# relay_interface_v2.net
KiCad netlist of a schematic drawn in EAGLE
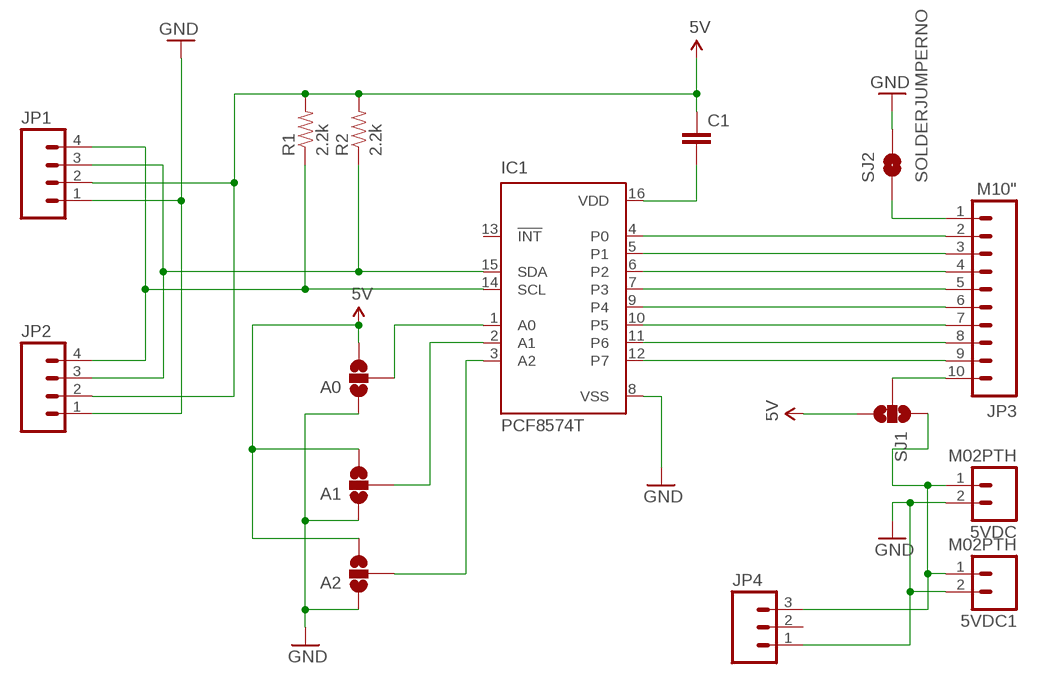
[diagram p0: schematic, sheet 1]

(export (version "E")
  (design (tool "Eeschema 10.0.6"))
  (components
    (comp (ref "5VDC")
      (value "M02PTH")
      (footprint "eagle-import:1X02")
      (libsource (lib "eagle-import") (part "M02PTH"))
    )
    (comp (ref "5VDC1")
      (value "M02PTH")
      (footprint "eagle-import:1X02")
      (libsource (lib "eagle-import") (part "M02PTH"))
    )
    (comp (ref "A0")
      (value "SOLDERJUMPER_2WAYS")
      (footprint "eagle-import:SJ_3")
      (libsource (lib "eagle-import") (part "SOLDERJUMPER_2WAYS"))
    )
    (comp (ref "A1")
      (value "SOLDERJUMPER_2WAYS")
      (footprint "eagle-import:SJ_3")
      (libsource (lib "eagle-import") (part "SOLDERJUMPER_2WAYS"))
    )
    (comp (ref "A2")
      (value "SOLDERJUMPER_2WAYS")
      (footprint "eagle-import:SJ_3")
      (libsource (lib "eagle-import") (part "SOLDERJUMPER_2WAYS"))
    )
    (comp (ref "C1")
      (value "CAPPTH2")
      (footprint "eagle-import:CAP-PTH-SMALL2")
      (libsource (lib "eagle-import") (part "CAPPTH2"))
    )
    (comp (ref "IC1")
      (value "PCF8574T")
      (footprint "eagle-import:SO16W")
      (libsource (lib "eagle-import") (part "PCF8574T"))
    )
    (comp (ref "JP1")
      (value "M04PTH")
      (footprint "eagle-import:1X04")
      (libsource (lib "eagle-import") (part "M04PTH"))
    )
    (comp (ref "JP2")
      (value "M04PTH")
      (footprint "eagle-import:1X04")
      (libsource (lib "eagle-import") (part "M04PTH"))
    )
    (comp (ref "JP3")
      (value "M10\"")
      (footprint "eagle-import:1X10")
      (libsource (lib "eagle-import") (part "M10{dblquote}"))
    )
    (comp (ref "JP4")
      (value "M03PTH")
      (footprint "eagle-import:1X03")
      (libsource (lib "eagle-import") (part "M03PTH"))
    )
    (comp (ref "R1")
      (value "2.2k")
      (footprint "eagle-import:1206")
      (libsource (lib "eagle-import") (part "RESISTOR1206"))
    )
    (comp (ref "R2")
      (value "2.2k")
      (footprint "eagle-import:1206")
      (libsource (lib "eagle-import") (part "RESISTOR1206"))
    )
    (comp (ref "SJ1")
      (value "SOLDERJUMPER_2WAYS")
      (footprint "eagle-import:SJ_3")
      (libsource (lib "eagle-import") (part "SOLDERJUMPER_2WAYS"))
    )
    (comp (ref "SJ2")
      (value "SOLDERJUMPERNO")
      (footprint "eagle-import:SJ_2S-NO")
      (libsource (lib "eagle-import") (part "SOLDERJUMPERNO"))
    )
  )
  (nets
    (net (code "1") (name "5V") (class "Default")
      (node (ref "A0") (pin "3") (pinfunction "3_3") (pintype "passive"))
      (node (ref "A1") (pin "3") (pinfunction "3_3") (pintype "passive"))
      (node (ref "A2") (pin "3") (pinfunction "3_3") (pintype "passive"))
      (node (ref "C1") (pin "1") (pinfunction "1_1") (pintype "passive"))
      (node (ref "JP1") (pin "2") (pinfunction "2_2") (pintype "passive"))
      (node (ref "JP2") (pin "2") (pinfunction "2_2") (pintype "passive"))
      (node (ref "R1") (pin "2") (pinfunction "2_2") (pintype "passive"))
      (node (ref "R2") (pin "2") (pinfunction "2_2") (pintype "passive"))
      (node (ref "SJ1") (pin "3") (pinfunction "3_3") (pintype "passive"))
    )
    (net (code "2") (name "GND") (class "Default")
      (node (ref "5VDC") (pin "2") (pinfunction "2_2") (pintype "passive"))
      (node (ref "5VDC1") (pin "2") (pinfunction "2_2") (pintype "passive"))
      (node (ref "A0") (pin "1") (pinfunction "1_1") (pintype "passive"))
      (node (ref "A1") (pin "1") (pinfunction "1_1") (pintype "passive"))
      (node (ref "A2") (pin "1") (pinfunction "1_1") (pintype "passive"))
      (node (ref "IC1") (pin "8") (pinfunction "VSS_8") (pintype "power_in"))
      (node (ref "JP1") (pin "1") (pinfunction "1_1") (pintype "passive"))
      (node (ref "JP2") (pin "1") (pinfunction "1_1") (pintype "passive"))
      (node (ref "JP4") (pin "1") (pinfunction "1_1") (pintype "passive"))
      (node (ref "SJ2") (pin "2") (pinfunction "2_2") (pintype "passive"))
    )
    (net (code "3") (name "Net-(5VDC-Pad1)") (class "Default")
      (node (ref "5VDC") (pin "1") (pinfunction "1_1") (pintype "passive"))
      (node (ref "5VDC1") (pin "1") (pinfunction "1_1") (pintype "passive"))
      (node (ref "JP4") (pin "3") (pinfunction "3_3") (pintype "passive"))
      (node (ref "SJ1") (pin "1") (pinfunction "1_1") (pintype "passive"))
    )
    (net (code "4") (name "Net-(IC1-A0)") (class "Default")
      (node (ref "A0") (pin "2") (pinfunction "2_2") (pintype "passive"))
      (node (ref "IC1") (pin "1") (pinfunction "A0_1") (pintype "input"))
    )
    (net (code "5") (name "Net-(IC1-A1)") (class "Default")
      (node (ref "A1") (pin "2") (pinfunction "2_2") (pintype "passive"))
      (node (ref "IC1") (pin "2") (pinfunction "A1_2") (pintype "input"))
    )
    (net (code "6") (name "Net-(IC1-A2)") (class "Default")
      (node (ref "A2") (pin "2") (pinfunction "2_2") (pintype "passive"))
      (node (ref "IC1") (pin "3") (pinfunction "A2_3") (pintype "input"))
    )
    (net (code "7") (name "Net-(IC1-P0)") (class "Default")
      (node (ref "IC1") (pin "4") (pinfunction "P0_4") (pintype "bidirectional"))
      (node (ref "JP3") (pin "2") (pinfunction "2_2") (pintype "passive"))
    )
    (net (code "8") (name "Net-(IC1-P1)") (class "Default")
      (node (ref "IC1") (pin "5") (pinfunction "P1_5") (pintype "bidirectional"))
      (node (ref "JP3") (pin "3") (pinfunction "3_3") (pintype "passive"))
    )
    (net (code "9") (name "Net-(IC1-P2)") (class "Default")
      (node (ref "IC1") (pin "6") (pinfunction "P2_6") (pintype "bidirectional"))
      (node (ref "JP3") (pin "4") (pinfunction "4_4") (pintype "passive"))
    )
    (net (code "10") (name "Net-(IC1-P3)") (class "Default")
      (node (ref "IC1") (pin "7") (pinfunction "P3_7") (pintype "bidirectional"))
      (node (ref "JP3") (pin "5") (pinfunction "5_5") (pintype "passive"))
    )
    (net (code "11") (name "Net-(IC1-P4)") (class "Default")
      (node (ref "IC1") (pin "9") (pinfunction "P4_9") (pintype "bidirectional"))
      (node (ref "JP3") (pin "6") (pinfunction "6_6") (pintype "passive"))
    )
    (net (code "12") (name "Net-(IC1-P5)") (class "Default")
      (node (ref "IC1") (pin "10") (pinfunction "P5_10") (pintype "bidirectional"))
      (node (ref "JP3") (pin "7") (pinfunction "7_7") (pintype "passive"))
    )
    (net (code "13") (name "Net-(IC1-P6)") (class "Default")
      (node (ref "IC1") (pin "11") (pinfunction "P6_11") (pintype "bidirectional"))
      (node (ref "JP3") (pin "8") (pinfunction "8_8") (pintype "passive"))
    )
    (net (code "14") (name "Net-(IC1-P7)") (class "Default")
      (node (ref "IC1") (pin "12") (pinfunction "P7_12") (pintype "bidirectional"))
      (node (ref "JP3") (pin "9") (pinfunction "9_9") (pintype "passive"))
    )
    (net (code "15") (name "Net-(IC1-SCL)") (class "Default")
      (node (ref "IC1") (pin "14") (pinfunction "SCL_14") (pintype "input"))
      (node (ref "JP1") (pin "4") (pinfunction "4_4") (pintype "passive"))
      (node (ref "JP2") (pin "4") (pinfunction "4_4") (pintype "passive"))
      (node (ref "R1") (pin "1") (pinfunction "1_1") (pintype "passive"))
    )
    (net (code "16") (name "Net-(IC1-SDA)") (class "Default")
      (node (ref "IC1") (pin "15") (pinfunction "SDA_15") (pintype "bidirectional"))
      (node (ref "JP1") (pin "3") (pinfunction "3_3") (pintype "passive"))
      (node (ref "JP2") (pin "3") (pinfunction "3_3") (pintype "passive"))
      (node (ref "R2") (pin "1") (pinfunction "1_1") (pintype "passive"))
    )
    (net (code "17") (name "Net-(IC1-VDD)") (class "Default")
      (node (ref "C1") (pin "2") (pinfunction "2_2") (pintype "passive"))
      (node (ref "IC1") (pin "16") (pinfunction "VDD_16") (pintype "power_in"))
    )
    (net (code "18") (name "Net-(JP3-Pad1)") (class "Default")
      (node (ref "JP3") (pin "1") (pinfunction "1_1") (pintype "passive"))
      (node (ref "SJ2") (pin "1") (pinfunction "1_1") (pintype "passive"))
    )
    (net (code "19") (name "Net-(JP3-Pad10)") (class "Default")
      (node (ref "JP3") (pin "10") (pinfunction "10_10") (pintype "passive"))
      (node (ref "SJ1") (pin "2") (pinfunction "2_2") (pintype "passive"))
    )
    (net (code "20") (name "unconnected-(IC1-~{INT}-Pad13)") (class "Default")
      (node (ref "IC1") (pin "13") (pinfunction "~{INT}_13") (pintype "output"))
    )
    (net (code "21") (name "unconnected-(JP4-Pad2)") (class "Default")
      (node (ref "JP4") (pin "2") (pinfunction "2_2") (pintype "passive"))
    )
  )
)
